# ssdf.net
KiCad netlist of a schematic drawn in EAGLE
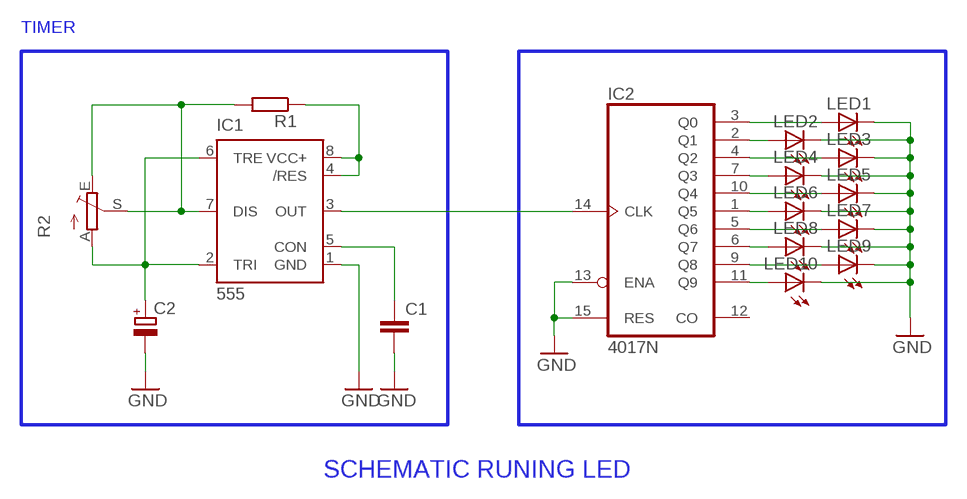
[diagram p0: schematic, sheet 1]

(export (version "E")
  (design (tool "Eeschema 10.0.6"))
  (components
    (comp (ref "C1")
      (value "C-EU050-025X075")
      (footprint "eagle-import:C050-025X075")
      (libsource (lib "eagle-import") (part "C-EU050-025X075"))
    )
    (comp (ref "C2")
      (value "CPOL-EUE2-5")
      (footprint "eagle-import:E2-5")
      (libsource (lib "eagle-import") (part "CPOL-EUE2-5"))
    )
    (comp (ref "IC1")
      (value "555")
      (footprint "eagle-import:DIP08-KIT")
      (libsource (lib "eagle-import") (part "555KIT"))
    )
    (comp (ref "IC2")
      (value "4017N")
      (footprint "eagle-import:DIL16")
      (libsource (lib "eagle-import") (part "4017N"))
    )
    (comp (ref "LED1")
      (value "LED3MM")
      (footprint "eagle-import:LED3MM")
      (libsource (lib "eagle-import") (part "LED3MM"))
    )
    (comp (ref "LED2")
      (value "LED3MM")
      (footprint "eagle-import:LED3MM")
      (libsource (lib "eagle-import") (part "LED3MM"))
    )
    (comp (ref "LED3")
      (value "LED3MM")
      (footprint "eagle-import:LED3MM")
      (libsource (lib "eagle-import") (part "LED3MM"))
    )
    (comp (ref "LED4")
      (value "LED3MM")
      (footprint "eagle-import:LED3MM")
      (libsource (lib "eagle-import") (part "LED3MM"))
    )
    (comp (ref "LED5")
      (value "LED3MM")
      (footprint "eagle-import:LED3MM")
      (libsource (lib "eagle-import") (part "LED3MM"))
    )
    (comp (ref "LED6")
      (value "LED3MM")
      (footprint "eagle-import:LED3MM")
      (libsource (lib "eagle-import") (part "LED3MM"))
    )
    (comp (ref "LED7")
      (value "LED3MM")
      (footprint "eagle-import:LED3MM")
      (libsource (lib "eagle-import") (part "LED3MM"))
    )
    (comp (ref "LED8")
      (value "LED3MM")
      (footprint "eagle-import:LED3MM")
      (libsource (lib "eagle-import") (part "LED3MM"))
    )
    (comp (ref "LED9")
      (value "LED3MM")
      (footprint "eagle-import:LED3MM")
      (libsource (lib "eagle-import") (part "LED3MM"))
    )
    (comp (ref "LED10")
      (value "LED3MM")
      (footprint "eagle-import:LED3MM")
      (libsource (lib "eagle-import") (part "LED3MM"))
    )
    (comp (ref "R1")
      (value "R-EU_0204/7")
      (footprint "eagle-import:0204_7")
      (libsource (lib "eagle-import") (part "R-EU_0204/7"))
    )
    (comp (ref "R2")
      (value "TRIM_EU-B25P")
      (footprint "eagle-import:B25P")
      (libsource (lib "eagle-import") (part "TRIM_EU-B25P"))
    )
  )
  (nets
    (net (code "1") (name "GND") (class "Default")
      (node (ref "C1") (pin "2") (pinfunction "2_2") (pintype "passive"))
      (node (ref "C2") (pin "-") (pinfunction "-_-") (pintype "passive"))
      (node (ref "IC1") (pin "1") (pinfunction "GND_1") (pintype "power_in"))
      (node (ref "IC2") (pin "13") (pinfunction "ENA_13") (pintype "input"))
      (node (ref "IC2") (pin "15") (pinfunction "RES_15") (pintype "input"))
      (node (ref "LED1") (pin "K") (pinfunction "C_K") (pintype "passive"))
      (node (ref "LED10") (pin "K") (pinfunction "C_K") (pintype "passive"))
      (node (ref "LED2") (pin "K") (pinfunction "C_K") (pintype "passive"))
      (node (ref "LED3") (pin "K") (pinfunction "C_K") (pintype "passive"))
      (node (ref "LED4") (pin "K") (pinfunction "C_K") (pintype "passive"))
      (node (ref "LED5") (pin "K") (pinfunction "C_K") (pintype "passive"))
      (node (ref "LED6") (pin "K") (pinfunction "C_K") (pintype "passive"))
      (node (ref "LED7") (pin "K") (pinfunction "C_K") (pintype "passive"))
      (node (ref "LED8") (pin "K") (pinfunction "C_K") (pintype "passive"))
      (node (ref "LED9") (pin "K") (pinfunction "C_K") (pintype "passive"))
    )
    (net (code "2") (name "Net-(IC1-CON)") (class "Default")
      (node (ref "C1") (pin "1") (pinfunction "1_1") (pintype "passive"))
      (node (ref "IC1") (pin "5") (pinfunction "CON_5") (pintype "input"))
    )
    (net (code "3") (name "Net-(IC1-DIS)") (class "Default")
      (node (ref "IC1") (pin "7") (pinfunction "DIS_7") (pintype "input"))
      (node (ref "R1") (pin "2") (pinfunction "2_2") (pintype "passive"))
      (node (ref "R2") (pin "E") (pinfunction "E_E") (pintype "passive"))
      (node (ref "R2") (pin "S") (pinfunction "S_S") (pintype "passive"))
    )
    (net (code "4") (name "Net-(IC1-OUT)") (class "Default")
      (node (ref "IC1") (pin "3") (pinfunction "OUT_3") (pintype "output"))
      (node (ref "IC2") (pin "14") (pinfunction "CLK_14") (pintype "input"))
    )
    (net (code "5") (name "Net-(IC1-TRE)") (class "Default")
      (node (ref "C2") (pin "+") (pinfunction "+_+") (pintype "passive"))
      (node (ref "IC1") (pin "2") (pinfunction "TRI_2") (pintype "input"))
      (node (ref "IC1") (pin "6") (pinfunction "TRE_6") (pintype "input"))
      (node (ref "R2") (pin "A") (pinfunction "A_A") (pintype "passive"))
    )
    (net (code "6") (name "Net-(IC1-VCC+)") (class "Default")
      (node (ref "IC1") (pin "4") (pinfunction "/RES_4") (pintype "input"))
      (node (ref "IC1") (pin "8") (pinfunction "VCC+_8") (pintype "power_in"))
      (node (ref "R1") (pin "1") (pinfunction "1_1") (pintype "passive"))
    )
    (net (code "7") (name "Net-(IC2A-Q0)") (class "Default")
      (node (ref "IC2") (pin "3") (pinfunction "Q0_3") (pintype "output"))
      (node (ref "LED1") (pin "A") (pinfunction "A_A") (pintype "passive"))
    )
    (net (code "8") (name "Net-(IC2A-Q1)") (class "Default")
      (node (ref "IC2") (pin "2") (pinfunction "Q1_2") (pintype "output"))
      (node (ref "LED2") (pin "A") (pinfunction "A_A") (pintype "passive"))
    )
    (net (code "9") (name "Net-(IC2A-Q2)") (class "Default")
      (node (ref "IC2") (pin "4") (pinfunction "Q2_4") (pintype "output"))
      (node (ref "LED3") (pin "A") (pinfunction "A_A") (pintype "passive"))
    )
    (net (code "10") (name "Net-(IC2A-Q3)") (class "Default")
      (node (ref "IC2") (pin "7") (pinfunction "Q3_7") (pintype "output"))
      (node (ref "LED4") (pin "A") (pinfunction "A_A") (pintype "passive"))
    )
    (net (code "11") (name "Net-(IC2A-Q4)") (class "Default")
      (node (ref "IC2") (pin "10") (pinfunction "Q4_10") (pintype "output"))
      (node (ref "LED5") (pin "A") (pinfunction "A_A") (pintype "passive"))
    )
    (net (code "12") (name "Net-(IC2A-Q5)") (class "Default")
      (node (ref "IC2") (pin "1") (pinfunction "Q5_1") (pintype "output"))
      (node (ref "LED6") (pin "A") (pinfunction "A_A") (pintype "passive"))
    )
    (net (code "13") (name "Net-(IC2A-Q6)") (class "Default")
      (node (ref "IC2") (pin "5") (pinfunction "Q6_5") (pintype "output"))
      (node (ref "LED7") (pin "A") (pinfunction "A_A") (pintype "passive"))
    )
    (net (code "14") (name "Net-(IC2A-Q7)") (class "Default")
      (node (ref "IC2") (pin "6") (pinfunction "Q7_6") (pintype "output"))
      (node (ref "LED8") (pin "A") (pinfunction "A_A") (pintype "passive"))
    )
    (net (code "15") (name "Net-(IC2A-Q8)") (class "Default")
      (node (ref "IC2") (pin "9") (pinfunction "Q8_9") (pintype "output"))
      (node (ref "LED9") (pin "A") (pinfunction "A_A") (pintype "passive"))
    )
    (net (code "16") (name "Net-(IC2A-Q9)") (class "Default")
      (node (ref "IC2") (pin "11") (pinfunction "Q9_11") (pintype "output"))
      (node (ref "LED10") (pin "A") (pinfunction "A_A") (pintype "passive"))
    )
    (net (code "17") (name "unconnected-(IC2A-CO-Pad12)") (class "Default")
      (node (ref "IC2") (pin "12") (pinfunction "CO_12") (pintype "output"))
    )
  )
)
